# 4_waffling60-MX_periferals.net
KiCad netlist of a schematic drawn in Altium Designer
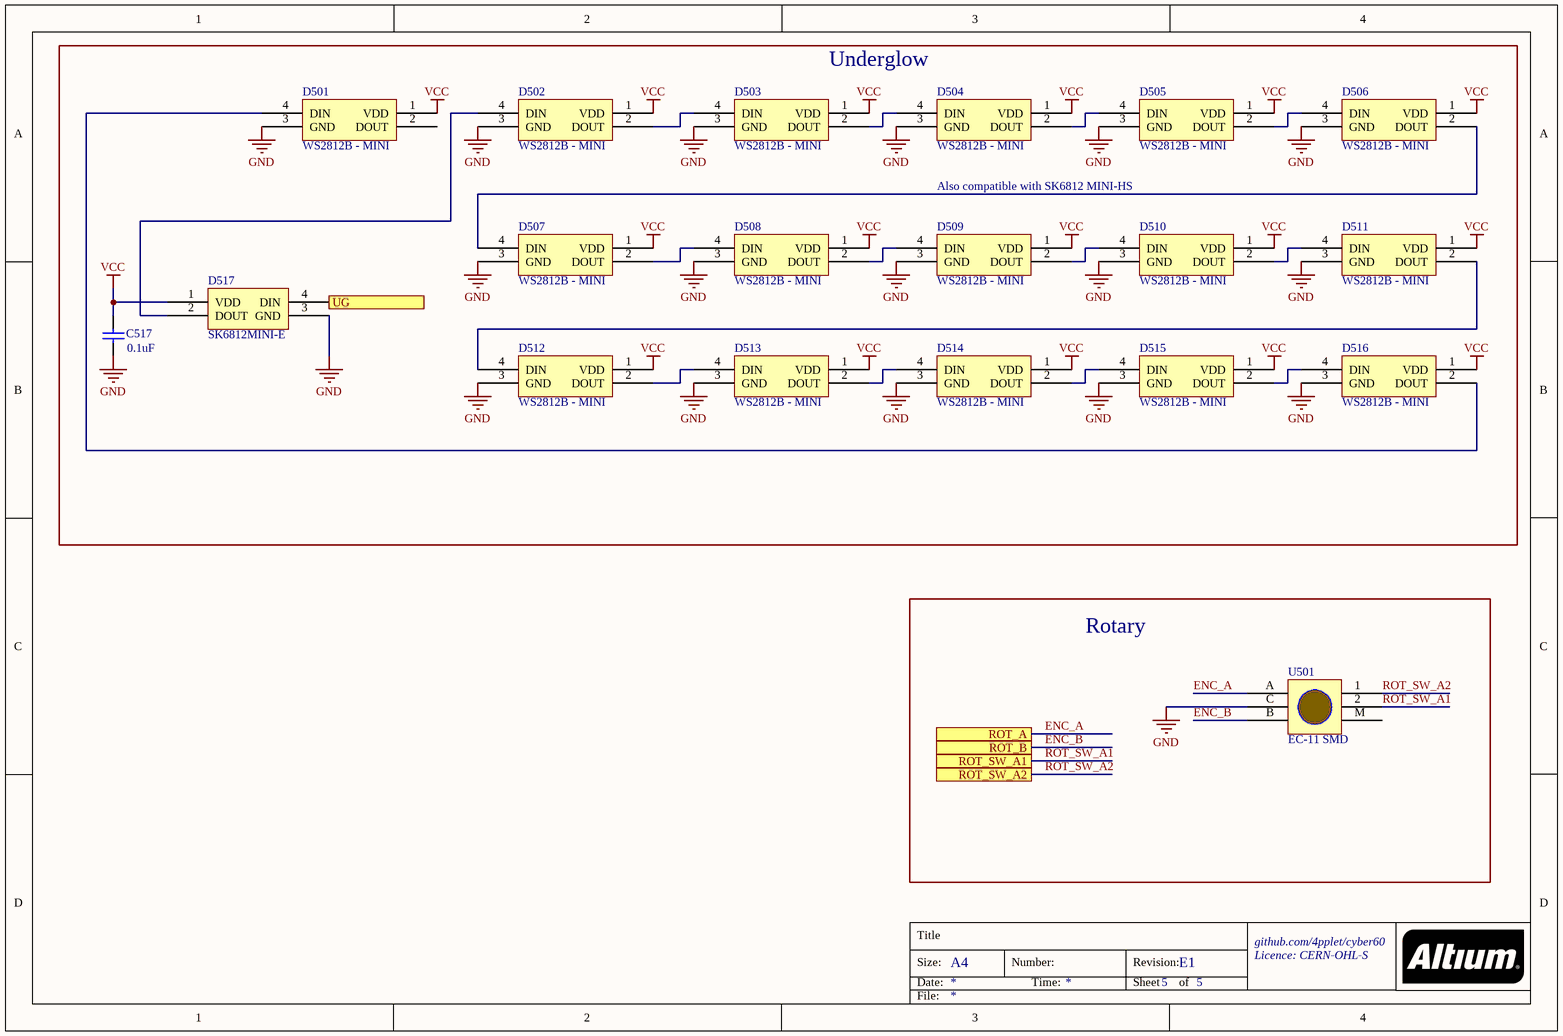
[diagram p0: 4_waffling60-MX_periferals.SchDoc]

(export (version "E")
  (design (tool "Eeschema 10.0.6"))
  (components
    (comp (ref "C517")
      (value "0.1uF")
      (footprint "C0603[1608]")
      (description "Capacitor")
      (fields (field (name "LCSC PART #") "C14663") (field (name "MRF.PART") "CC0603KRX7R9BB104"))
      (libsource (lib "Miscellaneous Devices") (part "Cap"))
    )
    (comp (ref "D501")
      (value "WS2812B - MINI")
      (footprint "WS2812B - 2020")
      (fields (field (name "LCSC PART #") "C965556") (field (name "MRF.PART") "WS2812C-2020"))
      (libsource (lib "Keebs") (part "WS2812B"))
    )
    (comp (ref "D502")
      (value "WS2812B - MINI")
      (footprint "WS2812B - 2020")
      (fields (field (name "LCSC PART #") "C965556") (field (name "MRF.PART") "WS2812C-2020"))
      (libsource (lib "Keebs") (part "WS2812B"))
    )
    (comp (ref "D503")
      (value "WS2812B - MINI")
      (footprint "WS2812B - 2020")
      (fields (field (name "LCSC PART #") "C965556") (field (name "MRF.PART") "WS2812C-2020"))
      (libsource (lib "Keebs") (part "WS2812B"))
    )
    (comp (ref "D504")
      (value "WS2812B - MINI")
      (footprint "WS2812B - 2020")
      (fields (field (name "LCSC PART #") "C965556") (field (name "MRF.PART") "WS2812C-2020"))
      (libsource (lib "Keebs") (part "WS2812B"))
    )
    (comp (ref "D505")
      (value "WS2812B - MINI")
      (footprint "WS2812B - 2020")
      (fields (field (name "LCSC PART #") "C965556") (field (name "MRF.PART") "WS2812C-2020"))
      (libsource (lib "Keebs") (part "WS2812B"))
    )
    (comp (ref "D506")
      (value "WS2812B - MINI")
      (footprint "WS2812B - 2020")
      (fields (field (name "LCSC PART #") "C965556") (field (name "MRF.PART") "WS2812C-2020"))
      (libsource (lib "Keebs") (part "WS2812B"))
    )
    (comp (ref "D507")
      (value "WS2812B - MINI")
      (footprint "WS2812B - 2020")
      (fields (field (name "LCSC PART #") "C965556") (field (name "MRF.PART") "WS2812C-2020"))
      (libsource (lib "Keebs") (part "WS2812B"))
    )
    (comp (ref "D508")
      (value "WS2812B - MINI")
      (footprint "WS2812B - 2020")
      (fields (field (name "LCSC PART #") "C965556") (field (name "MRF.PART") "WS2812C-2020"))
      (libsource (lib "Keebs") (part "WS2812B"))
    )
    (comp (ref "D509")
      (value "WS2812B - MINI")
      (footprint "WS2812B - 2020")
      (fields (field (name "LCSC PART #") "C965556") (field (name "MRF.PART") "WS2812C-2020"))
      (libsource (lib "Keebs") (part "WS2812B"))
    )
    (comp (ref "D510")
      (value "WS2812B - MINI")
      (footprint "WS2812B - 2020")
      (fields (field (name "LCSC PART #") "C965556") (field (name "MRF.PART") "WS2812C-2020"))
      (libsource (lib "Keebs") (part "WS2812B"))
    )
    (comp (ref "D511")
      (value "WS2812B - MINI")
      (footprint "WS2812B - 2020")
      (fields (field (name "LCSC PART #") "C965556") (field (name "MRF.PART") "WS2812C-2020"))
      (libsource (lib "Keebs") (part "WS2812B"))
    )
    (comp (ref "D512")
      (value "WS2812B - MINI")
      (footprint "WS2812B - 2020")
      (fields (field (name "LCSC PART #") "C965556") (field (name "MRF.PART") "WS2812C-2020"))
      (libsource (lib "Keebs") (part "WS2812B"))
    )
    (comp (ref "D513")
      (value "WS2812B - MINI")
      (footprint "WS2812B - 2020")
      (fields (field (name "LCSC PART #") "C965556") (field (name "MRF.PART") "WS2812C-2020"))
      (libsource (lib "Keebs") (part "WS2812B"))
    )
    (comp (ref "D514")
      (value "WS2812B - MINI")
      (footprint "WS2812B - 2020")
      (fields (field (name "LCSC PART #") "C965556") (field (name "MRF.PART") "WS2812C-2020"))
      (libsource (lib "Keebs") (part "WS2812B"))
    )
    (comp (ref "D515")
      (value "WS2812B - MINI")
      (footprint "WS2812B - 2020")
      (fields (field (name "LCSC PART #") "C965556") (field (name "MRF.PART") "WS2812C-2020"))
      (libsource (lib "Keebs") (part "WS2812B"))
    )
    (comp (ref "D516")
      (value "WS2812B - MINI")
      (footprint "WS2812B - 2020")
      (fields (field (name "LCSC PART #") "C965556") (field (name "MRF.PART") "WS2812C-2020"))
      (libsource (lib "Keebs") (part "WS2812B"))
    )
    (comp (ref "D517")
      (value "SK6812MINI-E")
      (footprint "SK6812MINI-E - shaped")
      (fields (field (name "LCSC PART #") "C524051") (field (name "MRF.PART") "DY-S352818/RGBC/6812-2T"))
      (libsource (lib "Keebs") (part "SK6812MINI-E"))
    )
    (comp (ref "U501") (value "EC-11 SMD") (footprint "EC11-SMD") (libsource (lib "Keebs") (part "EC-11")))
  )
  (nets
    (net (code "1") (name "/ENC_A") (class "Default")
      (node (ref "U501") (pin "A") (pinfunction "B_A") (pintype "passive"))
    )
    (net (code "2") (name "/ENC_B") (class "Default")
      (node (ref "U501") (pin "B") (pinfunction "B_B") (pintype "passive"))
    )
    (net (code "3") (name "/ROT_SW_A1") (class "Default")
      (node (ref "U501") (pin "2") (pinfunction "2_2") (pintype "passive"))
    )
    (net (code "4") (name "/ROT_SW_A2") (class "Default")
      (node (ref "U501") (pin "1") (pinfunction "1_1") (pintype "passive"))
    )
    (net (code "5") (name "/UG") (class "Default")
      (node (ref "D517") (pin "4") (pinfunction "DIN_4") (pintype "passive"))
    )
    (net (code "6") (name "GND") (class "Default")
      (node (ref "C517") (pin "1") (pinfunction "1_1") (pintype "passive"))
      (node (ref "D501") (pin "3") (pinfunction "GND_3") (pintype "passive"))
      (node (ref "D502") (pin "3") (pinfunction "GND_3") (pintype "passive"))
      (node (ref "D503") (pin "3") (pinfunction "GND_3") (pintype "passive"))
      (node (ref "D504") (pin "3") (pinfunction "GND_3") (pintype "passive"))
      (node (ref "D505") (pin "3") (pinfunction "GND_3") (pintype "passive"))
      (node (ref "D506") (pin "3") (pinfunction "GND_3") (pintype "passive"))
      (node (ref "D507") (pin "3") (pinfunction "GND_3") (pintype "passive"))
      (node (ref "D508") (pin "3") (pinfunction "GND_3") (pintype "passive"))
      (node (ref "D509") (pin "3") (pinfunction "GND_3") (pintype "passive"))
      (node (ref "D510") (pin "3") (pinfunction "GND_3") (pintype "passive"))
      (node (ref "D511") (pin "3") (pinfunction "GND_3") (pintype "passive"))
      (node (ref "D512") (pin "3") (pinfunction "GND_3") (pintype "passive"))
      (node (ref "D513") (pin "3") (pinfunction "GND_3") (pintype "passive"))
      (node (ref "D514") (pin "3") (pinfunction "GND_3") (pintype "passive"))
      (node (ref "D515") (pin "3") (pinfunction "GND_3") (pintype "passive"))
      (node (ref "D516") (pin "3") (pinfunction "GND_3") (pintype "passive"))
      (node (ref "D517") (pin "3") (pinfunction "GND_3") (pintype "passive"))
      (node (ref "U501") (pin "C") (pinfunction "C_C") (pintype "passive"))
    )
    (net (code "7") (name "Net-(D501-DIN)") (class "Default")
      (node (ref "D501") (pin "4") (pinfunction "DIN_4") (pintype "passive"))
      (node (ref "D516") (pin "2") (pinfunction "DOUT_2") (pintype "passive"))
    )
    (net (code "8") (name "Net-(D502-DIN)") (class "Default")
      (node (ref "D502") (pin "4") (pinfunction "DIN_4") (pintype "passive"))
      (node (ref "D517") (pin "2") (pinfunction "DOUT_2") (pintype "passive"))
    )
    (net (code "9") (name "Net-(D502-DOUT)") (class "Default")
      (node (ref "D502") (pin "2") (pinfunction "DOUT_2") (pintype "passive"))
      (node (ref "D503") (pin "4") (pinfunction "DIN_4") (pintype "passive"))
    )
    (net (code "10") (name "Net-(D503-DOUT)") (class "Default")
      (node (ref "D503") (pin "2") (pinfunction "DOUT_2") (pintype "passive"))
      (node (ref "D504") (pin "4") (pinfunction "DIN_4") (pintype "passive"))
    )
    (net (code "11") (name "Net-(D504-DOUT)") (class "Default")
      (node (ref "D504") (pin "2") (pinfunction "DOUT_2") (pintype "passive"))
      (node (ref "D505") (pin "4") (pinfunction "DIN_4") (pintype "passive"))
    )
    (net (code "12") (name "Net-(D505-DOUT)") (class "Default")
      (node (ref "D505") (pin "2") (pinfunction "DOUT_2") (pintype "passive"))
      (node (ref "D506") (pin "4") (pinfunction "DIN_4") (pintype "passive"))
    )
    (net (code "13") (name "Net-(D506-DOUT)") (class "Default")
      (node (ref "D506") (pin "2") (pinfunction "DOUT_2") (pintype "passive"))
      (node (ref "D507") (pin "4") (pinfunction "DIN_4") (pintype "passive"))
    )
    (net (code "14") (name "Net-(D507-DOUT)") (class "Default")
      (node (ref "D507") (pin "2") (pinfunction "DOUT_2") (pintype "passive"))
      (node (ref "D508") (pin "4") (pinfunction "DIN_4") (pintype "passive"))
    )
    (net (code "15") (name "Net-(D508-DOUT)") (class "Default")
      (node (ref "D508") (pin "2") (pinfunction "DOUT_2") (pintype "passive"))
      (node (ref "D509") (pin "4") (pinfunction "DIN_4") (pintype "passive"))
    )
    (net (code "16") (name "Net-(D509-DOUT)") (class "Default")
      (node (ref "D509") (pin "2") (pinfunction "DOUT_2") (pintype "passive"))
      (node (ref "D510") (pin "4") (pinfunction "DIN_4") (pintype "passive"))
    )
    (net (code "17") (name "Net-(D510-DOUT)") (class "Default")
      (node (ref "D510") (pin "2") (pinfunction "DOUT_2") (pintype "passive"))
      (node (ref "D511") (pin "4") (pinfunction "DIN_4") (pintype "passive"))
    )
    (net (code "18") (name "Net-(D511-DOUT)") (class "Default")
      (node (ref "D511") (pin "2") (pinfunction "DOUT_2") (pintype "passive"))
      (node (ref "D512") (pin "4") (pinfunction "DIN_4") (pintype "passive"))
    )
    (net (code "19") (name "Net-(D512-DOUT)") (class "Default")
      (node (ref "D512") (pin "2") (pinfunction "DOUT_2") (pintype "passive"))
      (node (ref "D513") (pin "4") (pinfunction "DIN_4") (pintype "passive"))
    )
    (net (code "20") (name "Net-(D513-DOUT)") (class "Default")
      (node (ref "D513") (pin "2") (pinfunction "DOUT_2") (pintype "passive"))
      (node (ref "D514") (pin "4") (pinfunction "DIN_4") (pintype "passive"))
    )
    (net (code "21") (name "Net-(D514-DOUT)") (class "Default")
      (node (ref "D514") (pin "2") (pinfunction "DOUT_2") (pintype "passive"))
      (node (ref "D515") (pin "4") (pinfunction "DIN_4") (pintype "passive"))
    )
    (net (code "22") (name "Net-(D515-DOUT)") (class "Default")
      (node (ref "D515") (pin "2") (pinfunction "DOUT_2") (pintype "passive"))
      (node (ref "D516") (pin "4") (pinfunction "DIN_4") (pintype "passive"))
    )
    (net (code "23") (name "VCC") (class "Default")
      (node (ref "C517") (pin "2") (pinfunction "2_2") (pintype "passive"))
      (node (ref "D501") (pin "1") (pinfunction "VDD_1") (pintype "passive"))
      (node (ref "D502") (pin "1") (pinfunction "VDD_1") (pintype "passive"))
      (node (ref "D503") (pin "1") (pinfunction "VDD_1") (pintype "passive"))
      (node (ref "D504") (pin "1") (pinfunction "VDD_1") (pintype "passive"))
      (node (ref "D505") (pin "1") (pinfunction "VDD_1") (pintype "passive"))
      (node (ref "D506") (pin "1") (pinfunction "VDD_1") (pintype "passive"))
      (node (ref "D507") (pin "1") (pinfunction "VDD_1") (pintype "passive"))
      (node (ref "D508") (pin "1") (pinfunction "VDD_1") (pintype "passive"))
      (node (ref "D509") (pin "1") (pinfunction "VDD_1") (pintype "passive"))
      (node (ref "D510") (pin "1") (pinfunction "VDD_1") (pintype "passive"))
      (node (ref "D511") (pin "1") (pinfunction "VDD_1") (pintype "passive"))
      (node (ref "D512") (pin "1") (pinfunction "VDD_1") (pintype "passive"))
      (node (ref "D513") (pin "1") (pinfunction "VDD_1") (pintype "passive"))
      (node (ref "D514") (pin "1") (pinfunction "VDD_1") (pintype "passive"))
      (node (ref "D515") (pin "1") (pinfunction "VDD_1") (pintype "passive"))
      (node (ref "D516") (pin "1") (pinfunction "VDD_1") (pintype "passive"))
      (node (ref "D517") (pin "1") (pinfunction "VDD_1") (pintype "passive"))
    )
    (net (code "24") (name "unconnected-(D501-DOUT-Pad2)") (class "Default")
      (node (ref "D501") (pin "2") (pinfunction "DOUT_2") (pintype "passive"))
    )
    (net (code "25") (name "unconnected-(U501-PadM)") (class "Default")
      (node (ref "U501") (pin "M") (pinfunction "M_M") (pintype "passive"))
    )
  )
)
